# Relay_ISOx16.net
KiCad netlist of a schematic drawn in EAGLE
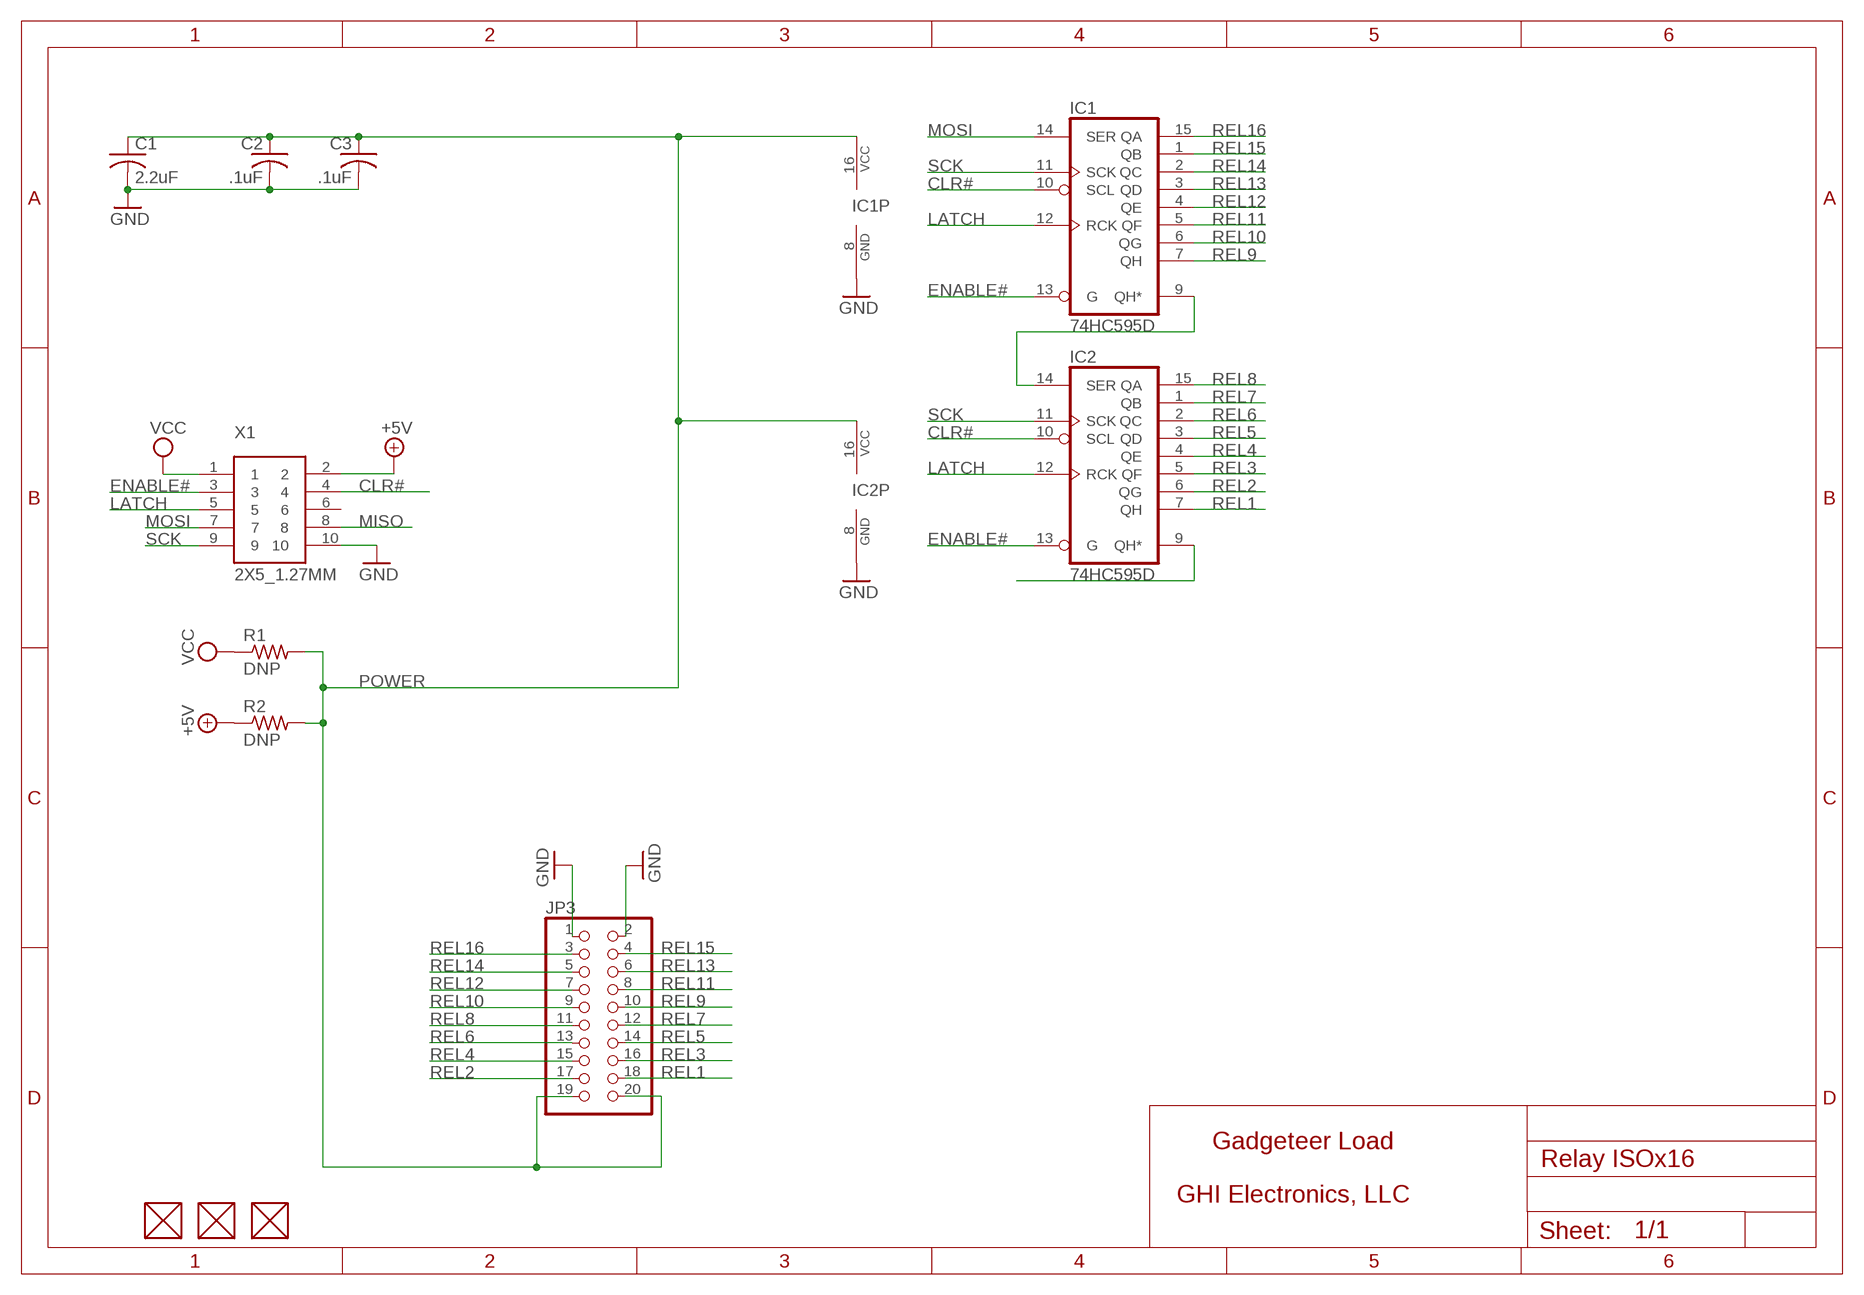
[diagram p0: schematic, sheet 1]

(export (version "E")
  (design (tool "Eeschema 10.0.6"))
  (components
    (comp (ref "C1")
      (value "2.2uF")
      (footprint "eagle-import:C0805K")
      (libsource (lib "eagle-import") (part "C-USC0805K"))
    )
    (comp (ref "C2")
      (value ".1uF")
      (footprint "eagle-import:C0603K")
      (libsource (lib "eagle-import") (part "C-USC0603K"))
    )
    (comp (ref "C3")
      (value ".1uF")
      (footprint "eagle-import:C0603K")
      (libsource (lib "eagle-import") (part "C-USC0603K"))
    )
    (comp (ref "FUD1")
      (value "FIDUCIAL")
      (footprint "eagle-import:FIDUCIAL_40MIL")
      (libsource (lib "eagle-import") (part "FIDUCIAL"))
    )
    (comp (ref "FUD2")
      (value "FIDUCIAL")
      (footprint "eagle-import:FIDUCIAL_40MIL")
      (libsource (lib "eagle-import") (part "FIDUCIAL"))
    )
    (comp (ref "FUD3")
      (value "FIDUCIAL")
      (footprint "eagle-import:FIDUCIAL_40MIL")
      (libsource (lib "eagle-import") (part "FIDUCIAL"))
    )
    (comp (ref "IC1")
      (value "74HC595D")
      (footprint "eagle-import:SO16")
      (libsource (lib "eagle-import") (part "74595DLS"))
    )
    (comp (ref "IC2")
      (value "74HC595D")
      (footprint "eagle-import:SO16")
      (libsource (lib "eagle-import") (part "74595DLS"))
    )
    (comp (ref "JP3")
      (value "PINHD-2X10")
      (footprint "eagle-import:2X10")
      (libsource (lib "eagle-import") (part "PINHD-2X10"))
    )
    (comp (ref "R1")
      (value "DNP")
      (footprint "eagle-import:R0603")
      (libsource (lib "eagle-import") (part "R-US_R0603"))
    )
    (comp (ref "R2")
      (value "DNP")
      (footprint "eagle-import:R0603")
      (libsource (lib "eagle-import") (part "R-US_R0603"))
    )
    (comp (ref "X1")
      (value "2X5_1.27MM")
      (footprint "eagle-import:2X5_1.27MM")
      (libsource (lib "eagle-import") (part "2X5_1.27MM"))
    )
  )
  (nets
    (net (code "1") (name "+5V") (class "Default")
      (node (ref "R2") (pin "1") (pinfunction "1_1") (pintype "passive"))
      (node (ref "X1") (pin "2") (pinfunction "2_2") (pintype "bidirectional"))
    )
    (net (code "2") (name "/CLR#") (class "Default")
      (node (ref "IC1") (pin "10") (pinfunction "SCL_10") (pintype "input"))
      (node (ref "IC2") (pin "10") (pinfunction "SCL_10") (pintype "input"))
      (node (ref "X1") (pin "4") (pinfunction "4_4") (pintype "bidirectional"))
    )
    (net (code "3") (name "/ENABLE#") (class "Default")
      (node (ref "IC1") (pin "13") (pinfunction "G_13") (pintype "input"))
      (node (ref "IC2") (pin "13") (pinfunction "G_13") (pintype "input"))
      (node (ref "X1") (pin "3") (pinfunction "3_3") (pintype "bidirectional"))
    )
    (net (code "4") (name "/LATCH") (class "Default")
      (node (ref "IC1") (pin "12") (pinfunction "RCK_12") (pintype "input"))
      (node (ref "IC2") (pin "12") (pinfunction "RCK_12") (pintype "input"))
      (node (ref "X1") (pin "5") (pinfunction "5_5") (pintype "bidirectional"))
    )
    (net (code "5") (name "/MISO") (class "Default")
      (node (ref "X1") (pin "8") (pinfunction "8_8") (pintype "bidirectional"))
    )
    (net (code "6") (name "/MOSI") (class "Default")
      (node (ref "IC1") (pin "14") (pinfunction "SER_14") (pintype "input"))
      (node (ref "X1") (pin "7") (pinfunction "7_7") (pintype "bidirectional"))
    )
    (net (code "7") (name "/POWER") (class "Default")
      (node (ref "C1") (pin "1") (pinfunction "1_1") (pintype "passive"))
      (node (ref "C2") (pin "1") (pinfunction "1_1") (pintype "passive"))
      (node (ref "C3") (pin "1") (pinfunction "1_1") (pintype "passive"))
      (node (ref "IC1") (pin "16") (pinfunction "VCC_16") (pintype "power_in"))
      (node (ref "IC2") (pin "16") (pinfunction "VCC_16") (pintype "power_in"))
      (node (ref "JP3") (pin "19") (pinfunction "19_19") (pintype "passive"))
      (node (ref "JP3") (pin "20") (pinfunction "20_20") (pintype "passive"))
      (node (ref "R1") (pin "2") (pinfunction "2_2") (pintype "passive"))
      (node (ref "R2") (pin "2") (pinfunction "2_2") (pintype "passive"))
    )
    (net (code "8") (name "/REL1") (class "Default")
      (node (ref "IC2") (pin "7") (pinfunction "QH_7") (pintype "tri_state"))
      (node (ref "JP3") (pin "18") (pinfunction "18_18") (pintype "passive"))
    )
    (net (code "9") (name "/REL2") (class "Default")
      (node (ref "IC2") (pin "6") (pinfunction "QG_6") (pintype "tri_state"))
      (node (ref "JP3") (pin "17") (pinfunction "17_17") (pintype "passive"))
    )
    (net (code "10") (name "/REL3") (class "Default")
      (node (ref "IC2") (pin "5") (pinfunction "QF_5") (pintype "tri_state"))
      (node (ref "JP3") (pin "16") (pinfunction "16_16") (pintype "passive"))
    )
    (net (code "11") (name "/REL4") (class "Default")
      (node (ref "IC2") (pin "4") (pinfunction "QE_4") (pintype "tri_state"))
      (node (ref "JP3") (pin "15") (pinfunction "15_15") (pintype "passive"))
    )
    (net (code "12") (name "/REL5") (class "Default")
      (node (ref "IC2") (pin "3") (pinfunction "QD_3") (pintype "tri_state"))
      (node (ref "JP3") (pin "14") (pinfunction "14_14") (pintype "passive"))
    )
    (net (code "13") (name "/REL6") (class "Default")
      (node (ref "IC2") (pin "2") (pinfunction "QC_2") (pintype "tri_state"))
      (node (ref "JP3") (pin "13") (pinfunction "13_13") (pintype "passive"))
    )
    (net (code "14") (name "/REL7") (class "Default")
      (node (ref "IC2") (pin "1") (pinfunction "QB_1") (pintype "tri_state"))
      (node (ref "JP3") (pin "12") (pinfunction "12_12") (pintype "passive"))
    )
    (net (code "15") (name "/REL8") (class "Default")
      (node (ref "IC2") (pin "15") (pinfunction "QA_15") (pintype "tri_state"))
      (node (ref "JP3") (pin "11") (pinfunction "11_11") (pintype "passive"))
    )
    (net (code "16") (name "/REL9") (class "Default")
      (node (ref "IC1") (pin "7") (pinfunction "QH_7") (pintype "tri_state"))
      (node (ref "JP3") (pin "10") (pinfunction "10_10") (pintype "passive"))
    )
    (net (code "17") (name "/REL10") (class "Default")
      (node (ref "IC1") (pin "6") (pinfunction "QG_6") (pintype "tri_state"))
      (node (ref "JP3") (pin "9") (pinfunction "9_9") (pintype "passive"))
    )
    (net (code "18") (name "/REL11") (class "Default")
      (node (ref "IC1") (pin "5") (pinfunction "QF_5") (pintype "tri_state"))
      (node (ref "JP3") (pin "8") (pinfunction "8_8") (pintype "passive"))
    )
    (net (code "19") (name "/REL12") (class "Default")
      (node (ref "IC1") (pin "4") (pinfunction "QE_4") (pintype "tri_state"))
      (node (ref "JP3") (pin "7") (pinfunction "7_7") (pintype "passive"))
    )
    (net (code "20") (name "/REL13") (class "Default")
      (node (ref "IC1") (pin "3") (pinfunction "QD_3") (pintype "tri_state"))
      (node (ref "JP3") (pin "6") (pinfunction "6_6") (pintype "passive"))
    )
    (net (code "21") (name "/REL14") (class "Default")
      (node (ref "IC1") (pin "2") (pinfunction "QC_2") (pintype "tri_state"))
      (node (ref "JP3") (pin "5") (pinfunction "5_5") (pintype "passive"))
    )
    (net (code "22") (name "/REL15") (class "Default")
      (node (ref "IC1") (pin "1") (pinfunction "QB_1") (pintype "tri_state"))
      (node (ref "JP3") (pin "4") (pinfunction "4_4") (pintype "passive"))
    )
    (net (code "23") (name "/REL16") (class "Default")
      (node (ref "IC1") (pin "15") (pinfunction "QA_15") (pintype "tri_state"))
      (node (ref "JP3") (pin "3") (pinfunction "3_3") (pintype "passive"))
    )
    (net (code "24") (name "/SCK") (class "Default")
      (node (ref "IC1") (pin "11") (pinfunction "SCK_11") (pintype "input"))
      (node (ref "IC2") (pin "11") (pinfunction "SCK_11") (pintype "input"))
      (node (ref "X1") (pin "9") (pinfunction "9_9") (pintype "bidirectional"))
    )
    (net (code "25") (name "GND") (class "Default")
      (node (ref "C1") (pin "2") (pinfunction "2_2") (pintype "passive"))
      (node (ref "C2") (pin "2") (pinfunction "2_2") (pintype "passive"))
      (node (ref "C3") (pin "2") (pinfunction "2_2") (pintype "passive"))
      (node (ref "IC1") (pin "8") (pinfunction "GND_8") (pintype "power_in"))
      (node (ref "IC2") (pin "8") (pinfunction "GND_8") (pintype "power_in"))
      (node (ref "JP3") (pin "1") (pinfunction "1_1") (pintype "passive"))
      (node (ref "JP3") (pin "2") (pinfunction "2_2") (pintype "passive"))
      (node (ref "X1") (pin "10") (pinfunction "10_10") (pintype "bidirectional"))
    )
    (net (code "26") (name "Net-(IC1A-QH*)") (class "Default")
      (node (ref "IC1") (pin "9") (pinfunction "QH*_9") (pintype "tri_state"))
      (node (ref "IC2") (pin "14") (pinfunction "SER_14") (pintype "input"))
    )
    (net (code "27") (name "VCC") (class "Default")
      (node (ref "R1") (pin "1") (pinfunction "1_1") (pintype "passive"))
      (node (ref "X1") (pin "1") (pinfunction "1_1") (pintype "bidirectional"))
    )
    (net (code "28") (name "unconnected-(FUD1-PadP$1)") (class "Default")
      (node (ref "FUD1") (pin "P$1") (pinfunction "P$1_P$1") (pintype "no_connect"))
    )
    (net (code "29") (name "unconnected-(FUD2-PadP$1)") (class "Default")
      (node (ref "FUD2") (pin "P$1") (pinfunction "P$1_P$1") (pintype "no_connect"))
    )
    (net (code "30") (name "unconnected-(FUD3-PadP$1)") (class "Default")
      (node (ref "FUD3") (pin "P$1") (pinfunction "P$1_P$1") (pintype "no_connect"))
    )
    (net (code "31") (name "unconnected-(IC2A-QH*-Pad9)") (class "Default")
      (node (ref "IC2") (pin "9") (pinfunction "QH*_9") (pintype "tri_state"))
    )
    (net (code "32") (name "unconnected-(X1-Pad6)") (class "Default")
      (node (ref "X1") (pin "6") (pinfunction "6_6") (pintype "bidirectional"))
    )
  )
)
